# kawa_devboard.net
KiCad netlist of a schematic drawn in EAGLE
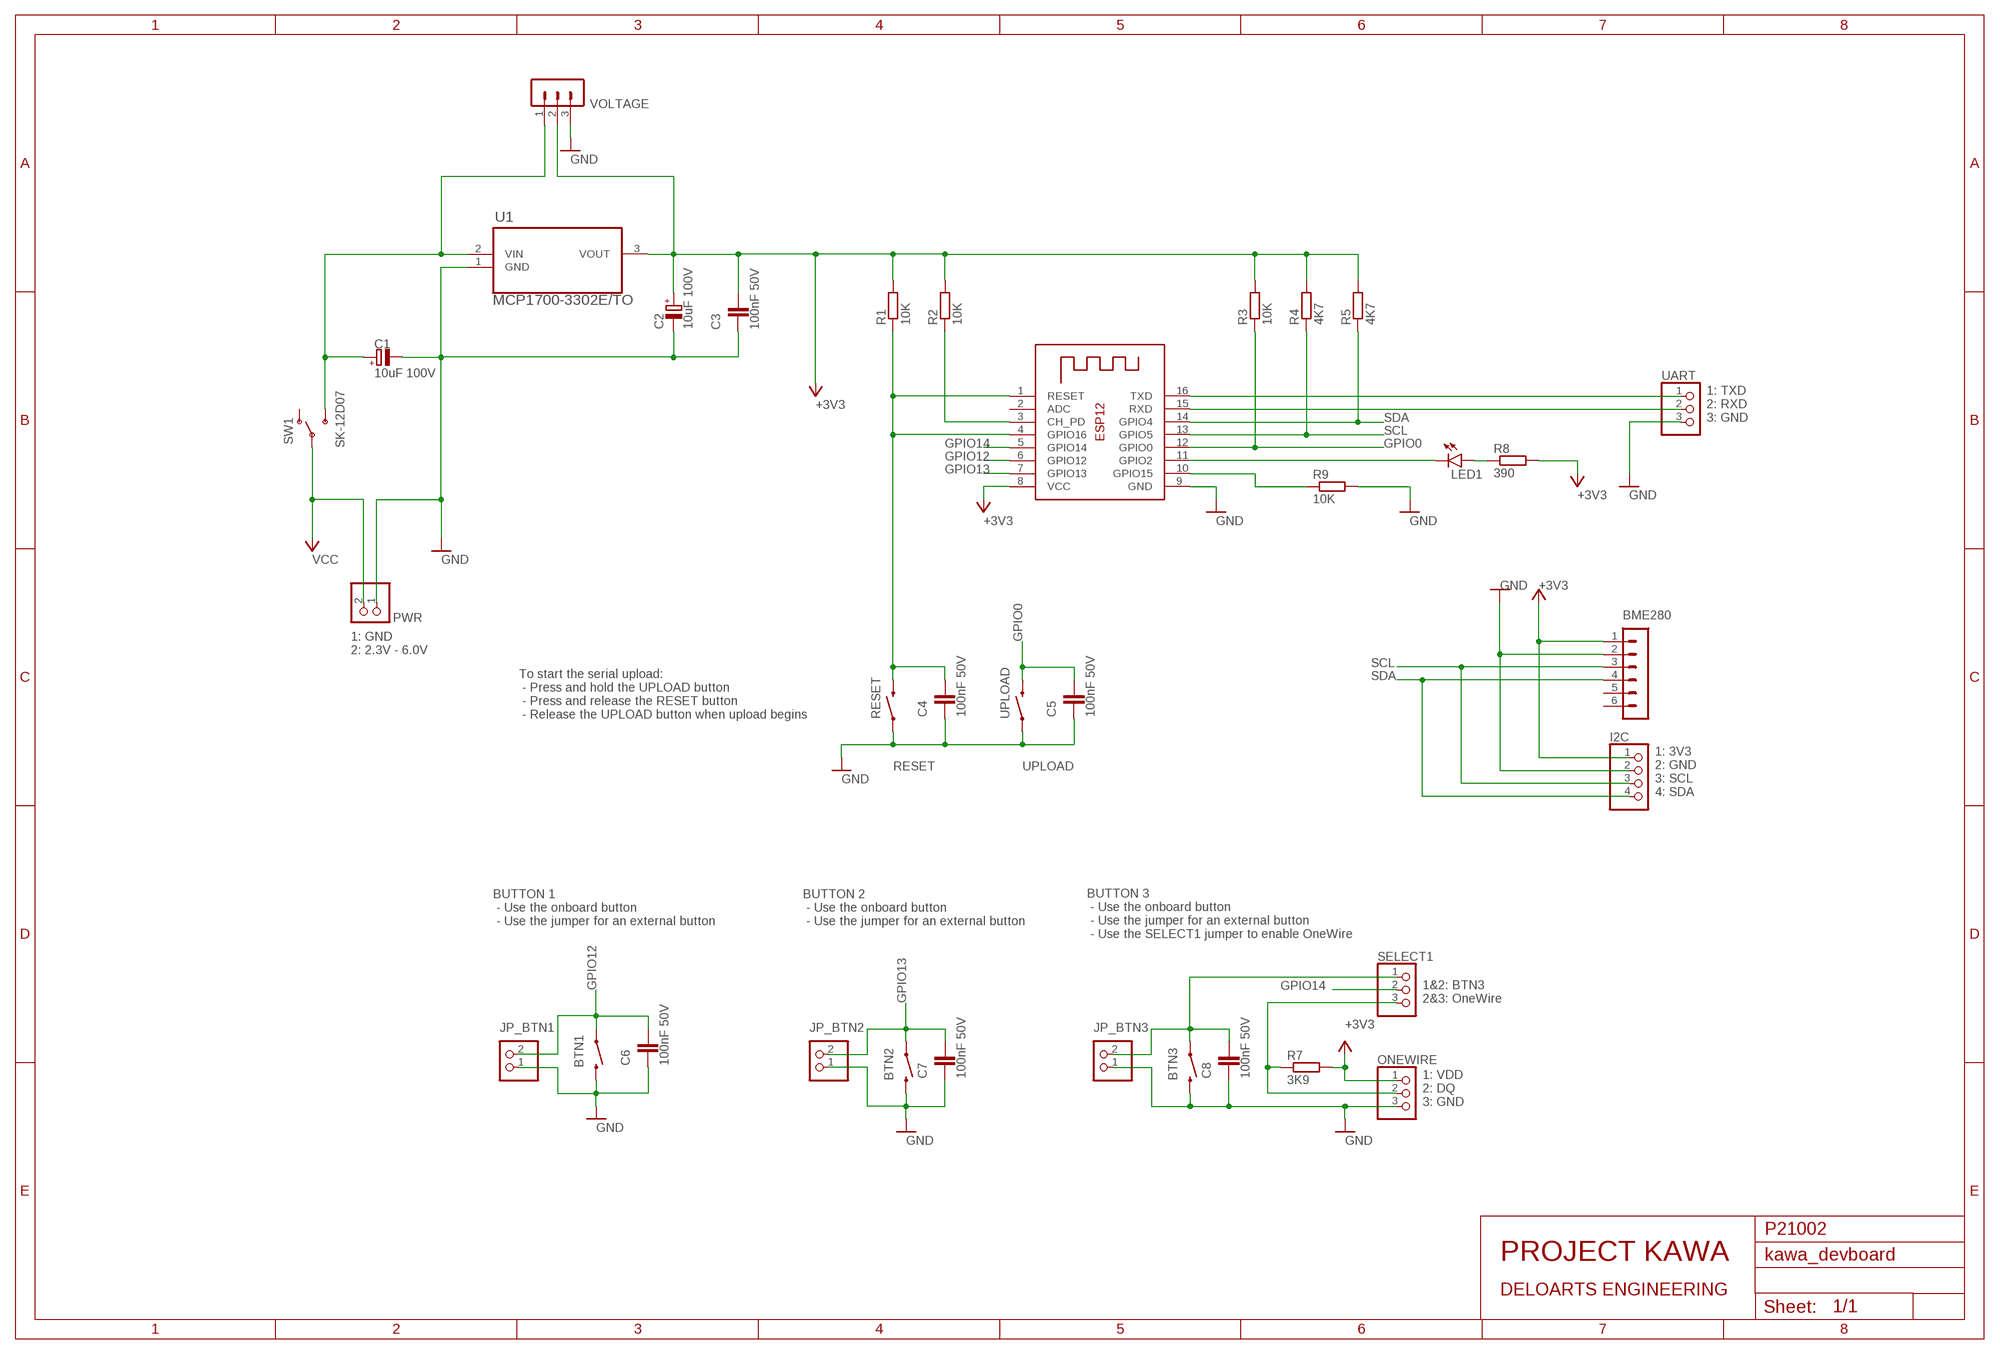
[diagram p0: schematic, sheet 1]

(export (version "E")
  (design (tool "Eeschema 10.0.6"))
  (components
    (comp (ref "BME280")
      (value "MA06-1")
      (footprint "eagle-import:MA06-1")
      (libsource (lib "eagle-import") (part "MA06-1"))
    )
    (comp (ref "BTN1")
      (value "MOMENTARY-SWITCH-SPST-PTH-6.0MM")
      (footprint "eagle-import:TACTILE_SWITCH_PTH_6.0MM")
      (libsource (lib "eagle-import") (part "MOMENTARY-SWITCH-SPST-PTH-6.0MM"))
    )
    (comp (ref "BTN2")
      (value "MOMENTARY-SWITCH-SPST-PTH-6.0MM")
      (footprint "eagle-import:TACTILE_SWITCH_PTH_6.0MM")
      (libsource (lib "eagle-import") (part "MOMENTARY-SWITCH-SPST-PTH-6.0MM"))
    )
    (comp (ref "BTN3")
      (value "MOMENTARY-SWITCH-SPST-PTH-6.0MM")
      (footprint "eagle-import:TACTILE_SWITCH_PTH_6.0MM")
      (libsource (lib "eagle-import") (part "MOMENTARY-SWITCH-SPST-PTH-6.0MM"))
    )
    (comp (ref "C1")
      (value "10uF 100V")
      (footprint "eagle-import:E2-5")
      (libsource (lib "eagle-import") (part "CPOL-EUE2-5"))
    )
    (comp (ref "C2")
      (value "10uF 100V")
      (footprint "eagle-import:E2-5")
      (libsource (lib "eagle-import") (part "CPOL-EUE2-5"))
    )
    (comp (ref "C3")
      (value "100nF 50V")
      (footprint "eagle-import:C2.5-3")
      (libsource (lib "eagle-import") (part "C2,5-3"))
    )
    (comp (ref "C4")
      (value "100nF 50V")
      (footprint "eagle-import:C2.5-3")
      (libsource (lib "eagle-import") (part "C2,5-3"))
    )
    (comp (ref "C5")
      (value "100nF 50V")
      (footprint "eagle-import:C2.5-3")
      (libsource (lib "eagle-import") (part "C2,5-3"))
    )
    (comp (ref "C6")
      (value "100nF 50V")
      (footprint "eagle-import:C2.5-3")
      (libsource (lib "eagle-import") (part "C2,5-3"))
    )
    (comp (ref "C7")
      (value "100nF 50V")
      (footprint "eagle-import:C2.5-3")
      (libsource (lib "eagle-import") (part "C2,5-3"))
    )
    (comp (ref "C8")
      (value "100nF 50V")
      (footprint "eagle-import:C2.5-3")
      (libsource (lib "eagle-import") (part "C2,5-3"))
    )
    (comp (ref "I2C")
      (value "PINHD-1X4")
      (footprint "eagle-import:1X04")
      (libsource (lib "eagle-import") (part "PINHD-1X4"))
    )
    (comp (ref "JP_BTN1")
      (value "PINHD-1X2/90")
      (footprint "eagle-import:1X02_90")
      (libsource (lib "eagle-import") (part "PINHD-1X2/90"))
    )
    (comp (ref "JP_BTN2")
      (value "PINHD-1X2/90")
      (footprint "eagle-import:1X02_90")
      (libsource (lib "eagle-import") (part "PINHD-1X2/90"))
    )
    (comp (ref "JP_BTN3")
      (value "PINHD-1X2/90")
      (footprint "eagle-import:1X02_90")
      (libsource (lib "eagle-import") (part "PINHD-1X2/90"))
    )
    (comp (ref "LED1")
      (value "LEDSFH480")
      (footprint "eagle-import:SFH480")
      (libsource (lib "eagle-import") (part "LEDSFH480"))
    )
    (comp (ref "ONEWIRE")
      (value "PINHD-1X3/90")
      (footprint "eagle-import:1X03_90")
      (libsource (lib "eagle-import") (part "PINHD-1X3/90"))
    )
    (comp (ref "PWR")
      (value "PINHD-1X2/90")
      (footprint "eagle-import:1X02_90")
      (libsource (lib "eagle-import") (part "PINHD-1X2/90"))
    )
    (comp (ref "R1")
      (value "10K")
      (footprint "eagle-import:0204_7")
      (libsource (lib "eagle-import") (part "R-EU_0204/7"))
    )
    (comp (ref "R2")
      (value "10K")
      (footprint "eagle-import:0204_7")
      (libsource (lib "eagle-import") (part "R-EU_0204/7"))
    )
    (comp (ref "R3")
      (value "10K")
      (footprint "eagle-import:0204_7")
      (libsource (lib "eagle-import") (part "R-EU_0204/7"))
    )
    (comp (ref "R4")
      (value "4K7")
      (footprint "eagle-import:0204_7")
      (libsource (lib "eagle-import") (part "R-EU_0204/7"))
    )
    (comp (ref "R5")
      (value "4K7")
      (footprint "eagle-import:0204_7")
      (libsource (lib "eagle-import") (part "R-EU_0204/7"))
    )
    (comp (ref "R7")
      (value "3K9")
      (footprint "eagle-import:0204_7")
      (libsource (lib "eagle-import") (part "R-EU_0204/7"))
    )
    (comp (ref "R8")
      (value "390")
      (footprint "eagle-import:0204_7")
      (libsource (lib "eagle-import") (part "R-EU_0204/7"))
    )
    (comp (ref "R9")
      (value "10K")
      (footprint "eagle-import:0204_7")
      (libsource (lib "eagle-import") (part "R-EU_0204/7"))
    )
    (comp (ref "RESET")
      (value "MOMENTARY-SWITCH-SPST-PTH-6.0MM")
      (footprint "eagle-import:TACTILE_SWITCH_PTH_6.0MM")
      (libsource (lib "eagle-import") (part "MOMENTARY-SWITCH-SPST-PTH-6.0MM"))
    )
    (comp (ref "SELECT1")
      (value "PINHD-1X3")
      (footprint "eagle-import:1X03")
      (libsource (lib "eagle-import") (part "PINHD-1X3"))
    )
    (comp (ref "SW1")
      (value "SK-12D07")
      (footprint "eagle-import:SK12SWITCH")
      (libsource (lib "eagle-import") (part "SK-12D07"))
    )
    (comp (ref "U1")
      (value "MCP1700-3302E/TO")
      (footprint "eagle-import:TO127P254X495-3")
      (fields (field (name "MF") "Microchip Technology"))
      (libsource (lib "eagle-import") (part "MCP1700-3302E/TO"))
    )
    (comp (ref "UART")
      (value "PINHD-1X3")
      (footprint "eagle-import:1X03")
      (libsource (lib "eagle-import") (part "PINHD-1X3"))
    )
    (comp (ref "UPLOAD")
      (value "MOMENTARY-SWITCH-SPST-PTH-6.0MM")
      (footprint "eagle-import:TACTILE_SWITCH_PTH_6.0MM")
      (libsource (lib "eagle-import") (part "MOMENTARY-SWITCH-SPST-PTH-6.0MM"))
    )
    (comp (ref "VOLTAGE")
      (value "MA03-1")
      (footprint "eagle-import:MA03-1")
      (libsource (lib "eagle-import") (part "MA03-1"))
    )
    (comp (ref "X1")
      (value "ESP-12")
      (footprint "eagle-import:ESP-12")
      (libsource (lib "eagle-import") (part "ESP-12"))
    )
  )
  (nets
    (net (code "1") (name "+3V3") (class "Default")
      (node (ref "BME280") (pin "1") (pinfunction "1_1") (pintype "passive"))
      (node (ref "C2") (pin "+") (pinfunction "+_+") (pintype "passive"))
      (node (ref "C3") (pin "1") (pinfunction "1_1") (pintype "passive"))
      (node (ref "I2C") (pin "1") (pinfunction "1_1") (pintype "passive"))
      (node (ref "ONEWIRE") (pin "1") (pinfunction "1_1") (pintype "passive"))
      (node (ref "R1") (pin "2") (pinfunction "2_2") (pintype "passive"))
      (node (ref "R2") (pin "2") (pinfunction "2_2") (pintype "passive"))
      (node (ref "R3") (pin "2") (pinfunction "2_2") (pintype "passive"))
      (node (ref "R4") (pin "2") (pinfunction "2_2") (pintype "passive"))
      (node (ref "R5") (pin "2") (pinfunction "2_2") (pintype "passive"))
      (node (ref "R7") (pin "2") (pinfunction "2_2") (pintype "passive"))
      (node (ref "R8") (pin "2") (pinfunction "2_2") (pintype "passive"))
      (node (ref "U1") (pin "3") (pinfunction "VOUT_3") (pintype "output"))
      (node (ref "VOLTAGE") (pin "2") (pinfunction "2_2") (pintype "passive"))
      (node (ref "X1") (pin "8") (pinfunction "VCC_8") (pintype "power_in"))
    )
    (net (code "2") (name "/GPIO0") (class "Default")
      (node (ref "C5") (pin "1") (pinfunction "1_1") (pintype "passive"))
      (node (ref "R3") (pin "1") (pinfunction "1_1") (pintype "passive"))
      (node (ref "UPLOAD") (pin "3") (pinfunction "2_3") (pintype "passive"))
      (node (ref "X1") (pin "12") (pinfunction "GPIO0_12") (pintype "bidirectional"))
    )
    (net (code "3") (name "/GPIO12") (class "Default")
      (node (ref "BTN1") (pin "1") (pinfunction "1_1") (pintype "passive"))
      (node (ref "C6") (pin "1") (pinfunction "1_1") (pintype "passive"))
      (node (ref "JP_BTN1") (pin "2") (pinfunction "2_2") (pintype "passive"))
      (node (ref "X1") (pin "6") (pinfunction "GPIO12_6") (pintype "bidirectional"))
    )
    (net (code "4") (name "/GPIO13") (class "Default")
      (node (ref "BTN2") (pin "1") (pinfunction "1_1") (pintype "passive"))
      (node (ref "C7") (pin "1") (pinfunction "1_1") (pintype "passive"))
      (node (ref "JP_BTN2") (pin "2") (pinfunction "2_2") (pintype "passive"))
      (node (ref "X1") (pin "7") (pinfunction "GPIO13_7") (pintype "bidirectional"))
    )
    (net (code "5") (name "/GPIO14") (class "Default")
      (node (ref "SELECT1") (pin "2") (pinfunction "2_2") (pintype "passive"))
      (node (ref "X1") (pin "5") (pinfunction "GPIO14_5") (pintype "bidirectional"))
    )
    (net (code "6") (name "/SCL") (class "Default")
      (node (ref "BME280") (pin "3") (pinfunction "3_3") (pintype "passive"))
      (node (ref "I2C") (pin "3") (pinfunction "3_3") (pintype "passive"))
      (node (ref "R4") (pin "1") (pinfunction "1_1") (pintype "passive"))
      (node (ref "X1") (pin "13") (pinfunction "GPIO5_13") (pintype "bidirectional"))
    )
    (net (code "7") (name "/SDA") (class "Default")
      (node (ref "BME280") (pin "4") (pinfunction "4_4") (pintype "passive"))
      (node (ref "I2C") (pin "4") (pinfunction "4_4") (pintype "passive"))
      (node (ref "R5") (pin "1") (pinfunction "1_1") (pintype "passive"))
      (node (ref "X1") (pin "14") (pinfunction "GPIO4_14") (pintype "bidirectional"))
    )
    (net (code "8") (name "GND") (class "Default")
      (node (ref "BME280") (pin "2") (pinfunction "2_2") (pintype "passive"))
      (node (ref "BTN1") (pin "3") (pinfunction "2_3") (pintype "passive"))
      (node (ref "BTN2") (pin "3") (pinfunction "2_3") (pintype "passive"))
      (node (ref "BTN3") (pin "3") (pinfunction "2_3") (pintype "passive"))
      (node (ref "C1") (pin "-") (pinfunction "-_-") (pintype "passive"))
      (node (ref "C2") (pin "-") (pinfunction "-_-") (pintype "passive"))
      (node (ref "C3") (pin "2") (pinfunction "2_2") (pintype "passive"))
      (node (ref "C4") (pin "2") (pinfunction "2_2") (pintype "passive"))
      (node (ref "C5") (pin "2") (pinfunction "2_2") (pintype "passive"))
      (node (ref "C6") (pin "2") (pinfunction "2_2") (pintype "passive"))
      (node (ref "C7") (pin "2") (pinfunction "2_2") (pintype "passive"))
      (node (ref "C8") (pin "2") (pinfunction "2_2") (pintype "passive"))
      (node (ref "I2C") (pin "2") (pinfunction "2_2") (pintype "passive"))
      (node (ref "JP_BTN1") (pin "1") (pinfunction "1_1") (pintype "passive"))
      (node (ref "JP_BTN2") (pin "1") (pinfunction "1_1") (pintype "passive"))
      (node (ref "JP_BTN3") (pin "1") (pinfunction "1_1") (pintype "passive"))
      (node (ref "ONEWIRE") (pin "3") (pinfunction "3_3") (pintype "passive"))
      (node (ref "PWR") (pin "1") (pinfunction "1_1") (pintype "passive"))
      (node (ref "R9") (pin "2") (pinfunction "2_2") (pintype "passive"))
      (node (ref "RESET") (pin "1") (pinfunction "1_1") (pintype "passive"))
      (node (ref "U1") (pin "1") (pinfunction "GND_1") (pintype "passive"))
      (node (ref "UART") (pin "3") (pinfunction "3_3") (pintype "passive"))
      (node (ref "UPLOAD") (pin "1") (pinfunction "1_1") (pintype "passive"))
      (node (ref "VOLTAGE") (pin "3") (pinfunction "3_3") (pintype "passive"))
      (node (ref "X1") (pin "9") (pinfunction "GND_9") (pintype "power_in"))
    )
    (net (code "9") (name "Net-(BTN3-Pad1)") (class "Default")
      (node (ref "BTN3") (pin "1") (pinfunction "1_1") (pintype "passive"))
      (node (ref "C8") (pin "1") (pinfunction "1_1") (pintype "passive"))
      (node (ref "JP_BTN3") (pin "2") (pinfunction "2_2") (pintype "passive"))
      (node (ref "SELECT1") (pin "1") (pinfunction "1_1") (pintype "passive"))
    )
    (net (code "10") (name "Net-(LED1-C)") (class "Default")
      (node (ref "LED1") (pin "K") (pinfunction "C_K") (pintype "passive"))
      (node (ref "X1") (pin "11") (pinfunction "GPIO2_11") (pintype "bidirectional"))
    )
    (net (code "11") (name "Net-(LED1-PadA)") (class "Default")
      (node (ref "LED1") (pin "A") (pinfunction "A_A") (pintype "passive"))
      (node (ref "R8") (pin "1") (pinfunction "1_1") (pintype "passive"))
    )
    (net (code "12") (name "Net-(ONEWIRE-Pad2)") (class "Default")
      (node (ref "ONEWIRE") (pin "2") (pinfunction "2_2") (pintype "passive"))
      (node (ref "R7") (pin "1") (pinfunction "1_1") (pintype "passive"))
      (node (ref "SELECT1") (pin "3") (pinfunction "3_3") (pintype "passive"))
    )
    (net (code "13") (name "Net-(RESET-2)") (class "Default")
      (node (ref "C4") (pin "1") (pinfunction "1_1") (pintype "passive"))
      (node (ref "R1") (pin "1") (pinfunction "1_1") (pintype "passive"))
      (node (ref "RESET") (pin "3") (pinfunction "2_3") (pintype "passive"))
      (node (ref "X1") (pin "1") (pinfunction "RESET_1") (pintype "input"))
      (node (ref "X1") (pin "4") (pinfunction "GPIO16_4") (pintype "bidirectional"))
    )
    (net (code "14") (name "Net-(SW1-S)") (class "Default")
      (node (ref "C1") (pin "+") (pinfunction "+_+") (pintype "passive"))
      (node (ref "SW1") (pin "IN") (pinfunction "S_IN") (pintype "passive"))
      (node (ref "U1") (pin "2") (pinfunction "VIN_2") (pintype "input"))
      (node (ref "VOLTAGE") (pin "1") (pinfunction "1_1") (pintype "passive"))
    )
    (net (code "15") (name "Net-(X1-CH_PD)") (class "Default")
      (node (ref "R2") (pin "1") (pinfunction "1_1") (pintype "passive"))
      (node (ref "X1") (pin "3") (pinfunction "CH_PD_3") (pintype "input"))
    )
    (net (code "16") (name "Net-(X1-GPIO15)") (class "Default")
      (node (ref "R9") (pin "1") (pinfunction "1_1") (pintype "passive"))
      (node (ref "X1") (pin "10") (pinfunction "GPIO15_10") (pintype "bidirectional"))
    )
    (net (code "17") (name "Net-(X1-RXD)") (class "Default")
      (node (ref "UART") (pin "2") (pinfunction "2_2") (pintype "passive"))
      (node (ref "X1") (pin "15") (pinfunction "RXD_15") (pintype "input"))
    )
    (net (code "18") (name "Net-(X1-TXD)") (class "Default")
      (node (ref "UART") (pin "1") (pinfunction "1_1") (pintype "passive"))
      (node (ref "X1") (pin "16") (pinfunction "TXD_16") (pintype "output"))
    )
    (net (code "19") (name "VCC") (class "Default")
      (node (ref "PWR") (pin "2") (pinfunction "2_2") (pintype "passive"))
      (node (ref "SW1") (pin "P2") (pinfunction "P_P2") (pintype "passive"))
    )
    (net (code "20") (name "unconnected-(BME280-Pad5)") (class "Default")
      (node (ref "BME280") (pin "5") (pinfunction "5_5") (pintype "passive"))
    )
    (net (code "21") (name "unconnected-(BME280-Pad6)") (class "Default")
      (node (ref "BME280") (pin "6") (pinfunction "6_6") (pintype "passive"))
    )
    (net (code "22") (name "unconnected-(SW1-O-PadP1)") (class "Default")
      (node (ref "SW1") (pin "P1") (pinfunction "O_P1") (pintype "passive"))
    )
    (net (code "23") (name "unconnected-(X1-ADC-Pad2)") (class "Default")
      (node (ref "X1") (pin "2") (pinfunction "ADC_2") (pintype "passive"))
    )
  )
)
